# circuito_mosfet.net
KiCad netlist of a schematic drawn in EAGLE
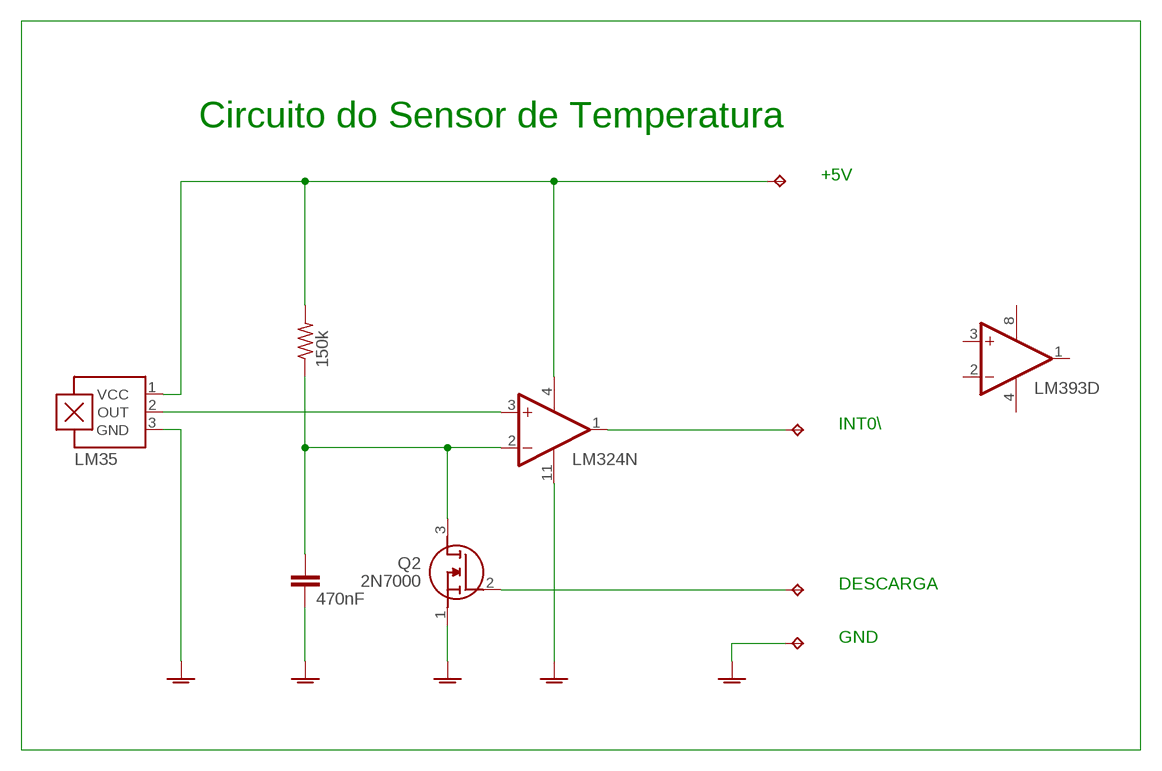
[diagram p0: schematic, sheet 1]

(export (version "E")
  (design (tool "Eeschema 10.0.6"))
  (components
    (comp (ref "C1")
      (value "470nF")
      (footprint "eagle-import:C2.5-3")
      (libsource (lib "eagle-import") (part "C2,5-3"))
    )
    (comp (ref "IC1")
      (value "LM324N")
      (footprint "eagle-import:DIL14")
      (libsource (lib "eagle-import") (part "LM324N"))
    )
    (comp (ref "IC2")
      (value "LM393D")
      (footprint "eagle-import:SO08")
      (libsource (lib "eagle-import") (part "LM393D"))
    )
    (comp (ref "IC3")
      (value "LM35")
      (footprint "eagle-import:SOT23-W")
      (fields (field (name "MF") "ALLEGRO MICROSYSTEMS, INC.") (field (name "MPN") "A1301ELHLT-T"))
      (libsource (lib "eagle-import") (part "A13?LH01"))
    )
    (comp (ref "Q2")
      (value "2N7000")
      (footprint "eagle-import:TO-92_(TO-226)")
      (fields (field (name "MOUSER_PART_NUMBER") "512-2N7000"))
      (libsource (lib "eagle-import") (part "2N7000"))
    )
    (comp (ref "R1")
      (value "150k")
      (footprint "eagle-import:0207_10")
      (libsource (lib "eagle-import") (part "R-US_0207/10"))
    )
    (comp (ref "TP1")
      (value "TPB1,27")
      (footprint "eagle-import:B1,27")
      (libsource (lib "eagle-import") (part "TPB1,27"))
    )
    (comp (ref "TP2")
      (value "TPB1,27")
      (footprint "eagle-import:B1,27")
      (libsource (lib "eagle-import") (part "TPB1,27"))
    )
    (comp (ref "TP3")
      (value "TPB1,27")
      (footprint "eagle-import:B1,27")
      (libsource (lib "eagle-import") (part "TPB1,27"))
    )
    (comp (ref "TP4")
      (value "TPB1,27")
      (footprint "eagle-import:B1,27")
      (libsource (lib "eagle-import") (part "TPB1,27"))
    )
  )
  (nets
    (net (code "1") (name "/V+") (class "Default")
      (node (ref "IC2") (pin "8") (pinfunction "V+_8") (pintype "power_in"))
    )
    (net (code "2") (name "/V-") (class "Default")
      (node (ref "IC2") (pin "4") (pinfunction "V-_4") (pintype "power_in"))
    )
    (net (code "3") (name "GNDA") (class "Default")
      (node (ref "C1") (pin "2") (pinfunction "2_2") (pintype "passive"))
      (node (ref "IC1") (pin "11") (pinfunction "V-_11") (pintype "power_in"))
      (node (ref "IC3") (pin "3") (pinfunction "GND_3") (pintype "power_in"))
      (node (ref "Q2") (pin "1") (pinfunction "S_1") (pintype "input"))
      (node (ref "TP2") (pin "TP") (pinfunction "TP_TP") (pintype "input"))
    )
    (net (code "4") (name "Net-(IC1A-+IN)") (class "Default")
      (node (ref "IC1") (pin "3") (pinfunction "+IN_3") (pintype "input"))
      (node (ref "IC3") (pin "2") (pinfunction "OUT_2") (pintype "output"))
    )
    (net (code "5") (name "Net-(IC1A--IN)") (class "Default")
      (node (ref "C1") (pin "1") (pinfunction "1_1") (pintype "passive"))
      (node (ref "IC1") (pin "2") (pinfunction "-IN_2") (pintype "input"))
      (node (ref "Q2") (pin "3") (pinfunction "D_3") (pintype "output"))
      (node (ref "R1") (pin "1") (pinfunction "1_1") (pintype "passive"))
    )
    (net (code "6") (name "Net-(IC1A-OUT)") (class "Default")
      (node (ref "IC1") (pin "1") (pinfunction "OUT_1") (pintype "output"))
      (node (ref "TP4") (pin "TP") (pinfunction "TP_TP") (pintype "input"))
    )
    (net (code "7") (name "Net-(IC1E-V+)") (class "Default")
      (node (ref "IC1") (pin "4") (pinfunction "V+_4") (pintype "power_in"))
      (node (ref "IC3") (pin "1") (pinfunction "VCC_1") (pintype "power_in"))
      (node (ref "R1") (pin "2") (pinfunction "2_2") (pintype "passive"))
      (node (ref "TP1") (pin "TP") (pinfunction "TP_TP") (pintype "input"))
    )
    (net (code "8") (name "Net-(Q2-G)") (class "Default")
      (node (ref "Q2") (pin "2") (pinfunction "G_2") (pintype "input"))
      (node (ref "TP3") (pin "TP") (pinfunction "TP_TP") (pintype "input"))
    )
    (net (code "9") (name "unconnected-(IC2A-+IN-Pad3)") (class "Default")
      (node (ref "IC2") (pin "3") (pinfunction "+IN_3") (pintype "input"))
    )
    (net (code "10") (name "unconnected-(IC2A--IN-Pad2)") (class "Default")
      (node (ref "IC2") (pin "2") (pinfunction "-IN_2") (pintype "input"))
    )
    (net (code "11") (name "unconnected-(IC2A-OUT-Pad1)") (class "Default")
      (node (ref "IC2") (pin "1") (pinfunction "OUT_1") (pintype "output"))
    )
  )
)
